# cable-adapter-12.net
KiCad netlist of a schematic drawn in EAGLE
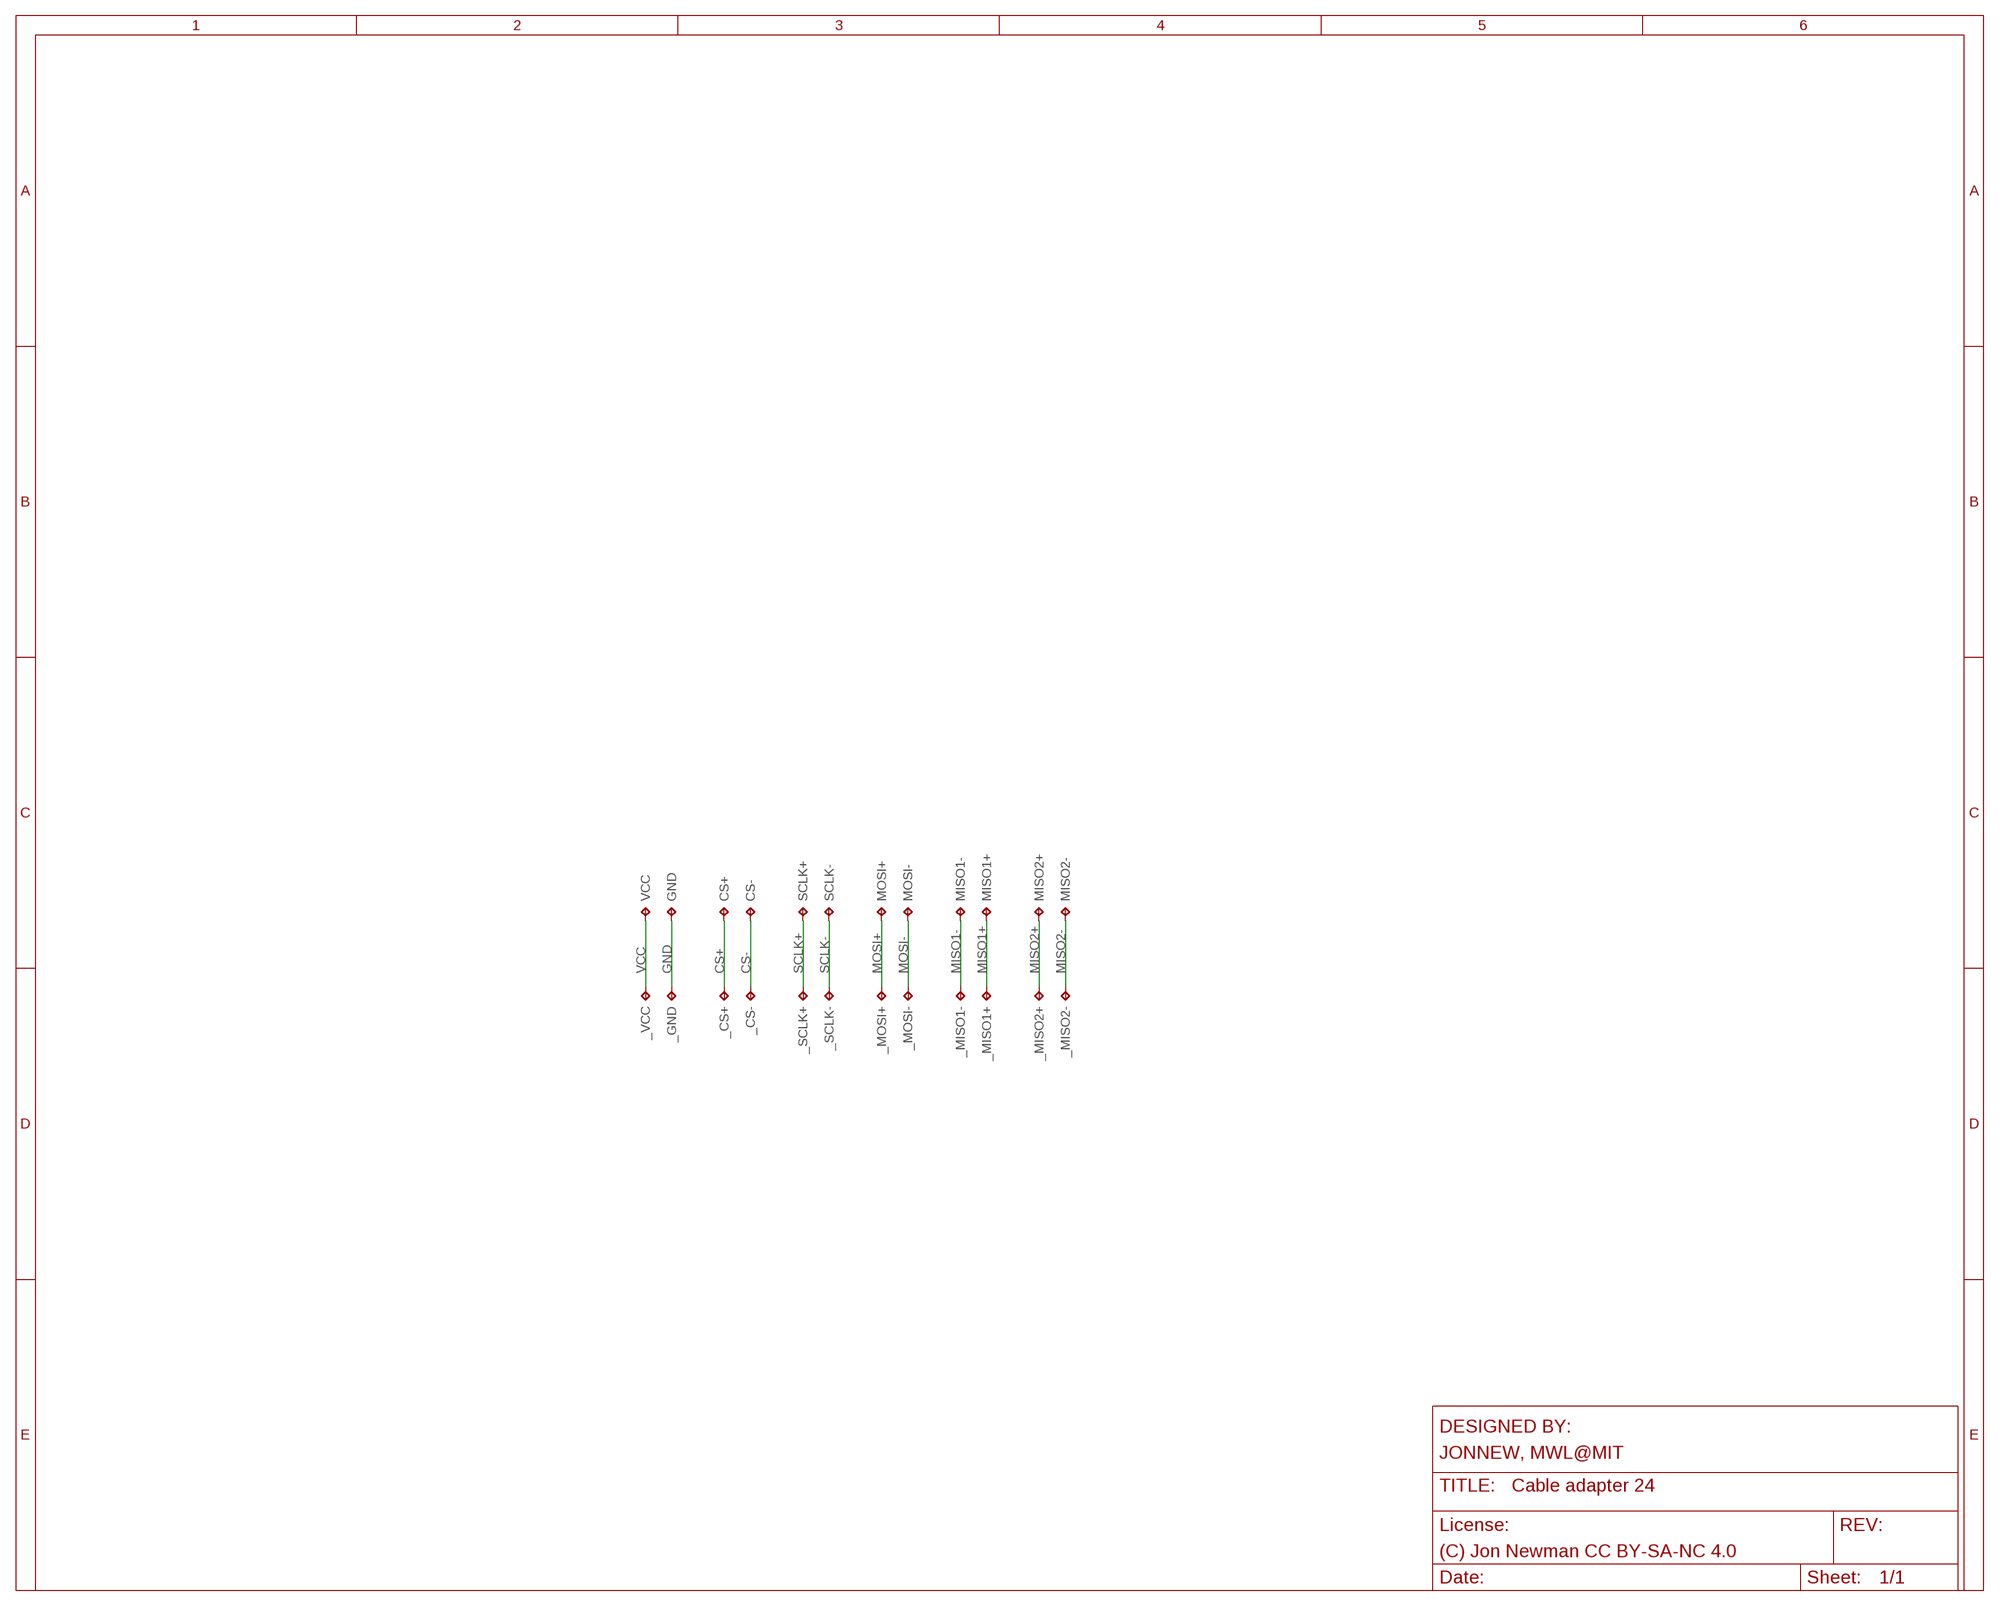
[diagram p0: schematic, sheet 1]

(export (version "E")
  (design (tool "Eeschema 10.0.6"))
  (components
    (comp (ref "CS+")
      (value "TP_SPI_WIRE+")
      (footprint "eagle-import:SPI_WIRE+")
      (libsource (lib "eagle-import") (part "TP_SPI_WIRE+"))
    )
    (comp (ref "CS-")
      (value "TP_SPI_WIRE+")
      (footprint "eagle-import:SPI_WIRE+")
      (libsource (lib "eagle-import") (part "TP_SPI_WIRE+"))
    )
    (comp (ref "GND")
      (value "TP_SPI_WIRE+")
      (footprint "eagle-import:SPI_WIRE+")
      (libsource (lib "eagle-import") (part "TP_SPI_WIRE+"))
    )
    (comp (ref "MISO1+")
      (value "TP_SPI_WIRE+")
      (footprint "eagle-import:SPI_WIRE+")
      (libsource (lib "eagle-import") (part "TP_SPI_WIRE+"))
    )
    (comp (ref "MISO1-")
      (value "TP_SPI_WIRE+")
      (footprint "eagle-import:SPI_WIRE+")
      (libsource (lib "eagle-import") (part "TP_SPI_WIRE+"))
    )
    (comp (ref "MISO2+")
      (value "TP_SPI_WIRE+")
      (footprint "eagle-import:SPI_WIRE+")
      (libsource (lib "eagle-import") (part "TP_SPI_WIRE+"))
    )
    (comp (ref "MISO2-")
      (value "TP_SPI_WIRE+")
      (footprint "eagle-import:SPI_WIRE+")
      (libsource (lib "eagle-import") (part "TP_SPI_WIRE+"))
    )
    (comp (ref "MOSI+")
      (value "TP_SPI_WIRE+")
      (footprint "eagle-import:SPI_WIRE+")
      (libsource (lib "eagle-import") (part "TP_SPI_WIRE+"))
    )
    (comp (ref "MOSI-")
      (value "TP_SPI_WIRE+")
      (footprint "eagle-import:SPI_WIRE+")
      (libsource (lib "eagle-import") (part "TP_SPI_WIRE+"))
    )
    (comp (ref "SCLK+")
      (value "TP_SPI_WIRE+")
      (footprint "eagle-import:SPI_WIRE+")
      (libsource (lib "eagle-import") (part "TP_SPI_WIRE+"))
    )
    (comp (ref "SCLK-")
      (value "TP_SPI_WIRE+")
      (footprint "eagle-import:SPI_WIRE+")
      (libsource (lib "eagle-import") (part "TP_SPI_WIRE+"))
    )
    (comp (ref "VCC")
      (value "TP_SPI_WIRE+")
      (footprint "eagle-import:SPI_WIRE+")
      (libsource (lib "eagle-import") (part "TP_SPI_WIRE+"))
    )
    (comp (ref "_CS+")
      (value "TP_SPI_WIRE+")
      (footprint "eagle-import:SPI_WIRE+")
      (libsource (lib "eagle-import") (part "TP_SPI_WIRE+"))
    )
    (comp (ref "_CS-")
      (value "TP_SPI_WIRE+")
      (footprint "eagle-import:SPI_WIRE+")
      (libsource (lib "eagle-import") (part "TP_SPI_WIRE+"))
    )
    (comp (ref "_GND")
      (value "TP_SPI_WIRE+")
      (footprint "eagle-import:SPI_WIRE+")
      (libsource (lib "eagle-import") (part "TP_SPI_WIRE+"))
    )
    (comp (ref "_MISO1+")
      (value "TP_SPI_WIRE+")
      (footprint "eagle-import:SPI_WIRE+")
      (libsource (lib "eagle-import") (part "TP_SPI_WIRE+"))
    )
    (comp (ref "_MISO1-")
      (value "TP_SPI_WIRE+")
      (footprint "eagle-import:SPI_WIRE+")
      (libsource (lib "eagle-import") (part "TP_SPI_WIRE+"))
    )
    (comp (ref "_MISO2+")
      (value "TP_SPI_WIRE+")
      (footprint "eagle-import:SPI_WIRE+")
      (libsource (lib "eagle-import") (part "TP_SPI_WIRE+"))
    )
    (comp (ref "_MISO2-")
      (value "TP_SPI_WIRE+")
      (footprint "eagle-import:SPI_WIRE+")
      (libsource (lib "eagle-import") (part "TP_SPI_WIRE+"))
    )
    (comp (ref "_MOSI+")
      (value "TP_SPI_WIRE+")
      (footprint "eagle-import:SPI_WIRE+")
      (libsource (lib "eagle-import") (part "TP_SPI_WIRE+"))
    )
    (comp (ref "_MOSI-")
      (value "TP_SPI_WIRE+")
      (footprint "eagle-import:SPI_WIRE+")
      (libsource (lib "eagle-import") (part "TP_SPI_WIRE+"))
    )
    (comp (ref "_SCLK+")
      (value "TP_SPI_WIRE+")
      (footprint "eagle-import:SPI_WIRE+")
      (libsource (lib "eagle-import") (part "TP_SPI_WIRE+"))
    )
    (comp (ref "_SCLK-")
      (value "TP_SPI_WIRE+")
      (footprint "eagle-import:SPI_WIRE+")
      (libsource (lib "eagle-import") (part "TP_SPI_WIRE+"))
    )
    (comp (ref "_VCC")
      (value "TP_SPI_WIRE+")
      (footprint "eagle-import:SPI_WIRE+")
      (libsource (lib "eagle-import") (part "TP_SPI_WIRE+"))
    )
  )
  (nets
    (net (code "1") (name "/CS+") (class "Default")
      (node (ref "CS+") (pin "P$1") (pinfunction "TP_P$1") (pintype "input"))
      (node (ref "_CS+") (pin "P$1") (pinfunction "TP_P$1") (pintype "input"))
    )
    (net (code "2") (name "/CS-") (class "Default")
      (node (ref "CS-") (pin "P$1") (pinfunction "TP_P$1") (pintype "input"))
      (node (ref "_CS-") (pin "P$1") (pinfunction "TP_P$1") (pintype "input"))
    )
    (net (code "3") (name "/GND") (class "Default")
      (node (ref "GND") (pin "P$1") (pinfunction "TP_P$1") (pintype "input"))
      (node (ref "_GND") (pin "P$1") (pinfunction "TP_P$1") (pintype "input"))
    )
    (net (code "4") (name "/MISO1+") (class "Default")
      (node (ref "MISO1+") (pin "P$1") (pinfunction "TP_P$1") (pintype "input"))
      (node (ref "_MISO1+") (pin "P$1") (pinfunction "TP_P$1") (pintype "input"))
    )
    (net (code "5") (name "/MISO1-") (class "Default")
      (node (ref "MISO1-") (pin "P$1") (pinfunction "TP_P$1") (pintype "input"))
      (node (ref "_MISO1-") (pin "P$1") (pinfunction "TP_P$1") (pintype "input"))
    )
    (net (code "6") (name "/MISO2+") (class "Default")
      (node (ref "MISO2+") (pin "P$1") (pinfunction "TP_P$1") (pintype "input"))
      (node (ref "_MISO2+") (pin "P$1") (pinfunction "TP_P$1") (pintype "input"))
    )
    (net (code "7") (name "/MISO2-") (class "Default")
      (node (ref "MISO2-") (pin "P$1") (pinfunction "TP_P$1") (pintype "input"))
      (node (ref "_MISO2-") (pin "P$1") (pinfunction "TP_P$1") (pintype "input"))
    )
    (net (code "8") (name "/MOSI+") (class "Default")
      (node (ref "MOSI+") (pin "P$1") (pinfunction "TP_P$1") (pintype "input"))
      (node (ref "_MOSI+") (pin "P$1") (pinfunction "TP_P$1") (pintype "input"))
    )
    (net (code "9") (name "/MOSI-") (class "Default")
      (node (ref "MOSI-") (pin "P$1") (pinfunction "TP_P$1") (pintype "input"))
      (node (ref "_MOSI-") (pin "P$1") (pinfunction "TP_P$1") (pintype "input"))
    )
    (net (code "10") (name "/SCLK+") (class "Default")
      (node (ref "SCLK+") (pin "P$1") (pinfunction "TP_P$1") (pintype "input"))
      (node (ref "_SCLK+") (pin "P$1") (pinfunction "TP_P$1") (pintype "input"))
    )
    (net (code "11") (name "/SCLK-") (class "Default")
      (node (ref "SCLK-") (pin "P$1") (pinfunction "TP_P$1") (pintype "input"))
      (node (ref "_SCLK-") (pin "P$1") (pinfunction "TP_P$1") (pintype "input"))
    )
    (net (code "12") (name "/VCC") (class "Default")
      (node (ref "VCC") (pin "P$1") (pinfunction "TP_P$1") (pintype "input"))
      (node (ref "_VCC") (pin "P$1") (pinfunction "TP_P$1") (pintype "input"))
    )
  )
)
